# hot_swap.net
KiCad netlist of a schematic drawn in EAGLE
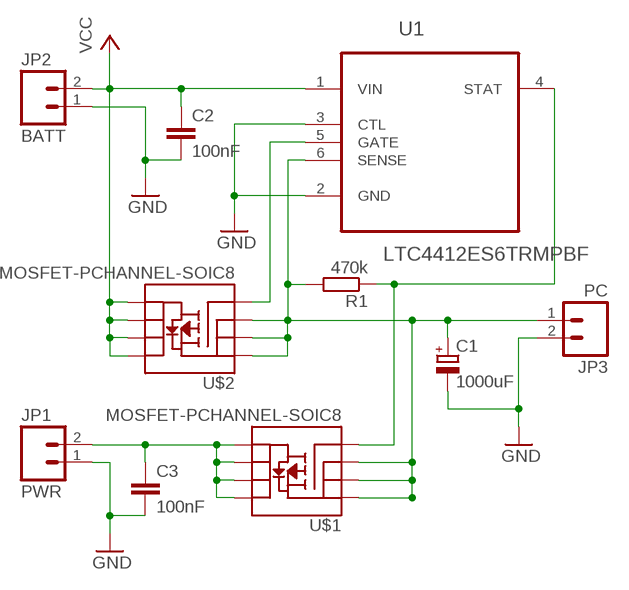
[diagram p0: schematic, sheet 1]

(export (version "E")
  (design (tool "Eeschema 10.0.6"))
  (components
    (comp (ref "C1")
      (value "1000uF")
      (footprint "eagle-import:E3,5-8")
      (libsource (lib "eagle-import") (part "CPOL-EUE3.5-8"))
    )
    (comp (ref "C2")
      (value "100nF")
      (footprint "eagle-import:C0603K")
      (libsource (lib "eagle-import") (part "C-EUC0603K"))
    )
    (comp (ref "C3")
      (value "100nF")
      (footprint "eagle-import:C0603K")
      (libsource (lib "eagle-import") (part "C-EUC0603K"))
    )
    (comp (ref "JP1")
      (value "PWR")
      (footprint "eagle-import:SCREWTERMINAL-3.5MM-2")
      (libsource (lib "eagle-import") (part "M023.5MM"))
    )
    (comp (ref "JP2")
      (value "BATT")
      (footprint "eagle-import:SCREWTERMINAL-3.5MM-2")
      (libsource (lib "eagle-import") (part "M023.5MM"))
    )
    (comp (ref "JP3")
      (value "PC")
      (footprint "eagle-import:SCREWTERMINAL-3.5MM-2")
      (libsource (lib "eagle-import") (part "M023.5MM"))
    )
    (comp (ref "R1")
      (value "470k")
      (footprint "eagle-import:R0603")
      (libsource (lib "eagle-import") (part "R-EU_R0603"))
    )
    (comp (ref "U$1")
      (value "MOSFET-PCHANNEL-SOIC8")
      (footprint "eagle-import:SO08")
      (libsource (lib "eagle-import") (part "MOSFET-PCHANNEL-SOIC8SOIC8"))
    )
    (comp (ref "U$2")
      (value "MOSFET-PCHANNEL-SOIC8")
      (footprint "eagle-import:SO08")
      (libsource (lib "eagle-import") (part "MOSFET-PCHANNEL-SOIC8SOIC8"))
    )
    (comp (ref "U1")
      (value "LTC4412ES6TRMPBF")
      (footprint "eagle-import:SOT95P280X100-6N")
      (fields (field (name "MPN") "LTC4412ES6#TRMPBF"))
      (libsource (lib "eagle-import") (part "LTC4412ES6TRMPBF"))
    )
  )
  (nets
    (net (code "1") (name "GND") (class "Default")
      (node (ref "C1") (pin "-") (pinfunction "-_-") (pintype "passive"))
      (node (ref "C2") (pin "2") (pinfunction "2_2") (pintype "passive"))
      (node (ref "C3") (pin "2") (pinfunction "2_2") (pintype "passive"))
      (node (ref "JP1") (pin "1") (pinfunction "1_1") (pintype "passive"))
      (node (ref "JP2") (pin "1") (pinfunction "1_1") (pintype "passive"))
      (node (ref "JP3") (pin "2") (pinfunction "2_2") (pintype "passive"))
      (node (ref "U1") (pin "2") (pinfunction "GND_2") (pintype "passive"))
      (node (ref "U1") (pin "3") (pinfunction "CTL_3") (pintype "input"))
    )
    (net (code "2") (name "Net-(C3-Pad1)") (class "Default")
      (node (ref "C3") (pin "1") (pinfunction "1_1") (pintype "passive"))
      (node (ref "JP1") (pin "2") (pinfunction "2_2") (pintype "passive"))
      (node (ref "U$1") (pin "5") (pinfunction "D_5") (pintype "bidirectional"))
      (node (ref "U$1") (pin "6") (pinfunction "D_6") (pintype "bidirectional"))
      (node (ref "U$1") (pin "7") (pinfunction "D_7") (pintype "bidirectional"))
      (node (ref "U$1") (pin "8") (pinfunction "D_8") (pintype "bidirectional"))
    )
    (net (code "3") (name "Net-(U$1-G)") (class "Default")
      (node (ref "R1") (pin "1") (pinfunction "1_1") (pintype "passive"))
      (node (ref "U$1") (pin "4") (pinfunction "G_4") (pintype "bidirectional"))
      (node (ref "U1") (pin "4") (pinfunction "STAT_4") (pintype "output"))
    )
    (net (code "4") (name "Net-(U$2-G)") (class "Default")
      (node (ref "U$2") (pin "4") (pinfunction "G_4") (pintype "bidirectional"))
      (node (ref "U1") (pin "5") (pinfunction "GATE_5") (pintype "input"))
    )
    (net (code "5") (name "Net-(U1-SENSE)") (class "Default")
      (node (ref "C1") (pin "+") (pinfunction "+_+") (pintype "passive"))
      (node (ref "JP3") (pin "1") (pinfunction "1_1") (pintype "passive"))
      (node (ref "R1") (pin "2") (pinfunction "2_2") (pintype "passive"))
      (node (ref "U$1") (pin "1") (pinfunction "S_1") (pintype "bidirectional"))
      (node (ref "U$1") (pin "2") (pinfunction "S_2") (pintype "bidirectional"))
      (node (ref "U$1") (pin "3") (pinfunction "S_3") (pintype "bidirectional"))
      (node (ref "U$2") (pin "1") (pinfunction "S_1") (pintype "bidirectional"))
      (node (ref "U$2") (pin "2") (pinfunction "S_2") (pintype "bidirectional"))
      (node (ref "U$2") (pin "3") (pinfunction "S_3") (pintype "bidirectional"))
      (node (ref "U1") (pin "6") (pinfunction "SENSE_6") (pintype "input"))
    )
    (net (code "6") (name "VCC") (class "Default")
      (node (ref "C2") (pin "1") (pinfunction "1_1") (pintype "passive"))
      (node (ref "JP2") (pin "2") (pinfunction "2_2") (pintype "passive"))
      (node (ref "U$2") (pin "5") (pinfunction "D_5") (pintype "bidirectional"))
      (node (ref "U$2") (pin "6") (pinfunction "D_6") (pintype "bidirectional"))
      (node (ref "U$2") (pin "7") (pinfunction "D_7") (pintype "bidirectional"))
      (node (ref "U$2") (pin "8") (pinfunction "D_8") (pintype "bidirectional"))
      (node (ref "U1") (pin "1") (pinfunction "VIN_1") (pintype "power_in"))
    )
  )
)
